# Switch.net
KiCad netlist of a schematic drawn in Altium Designer
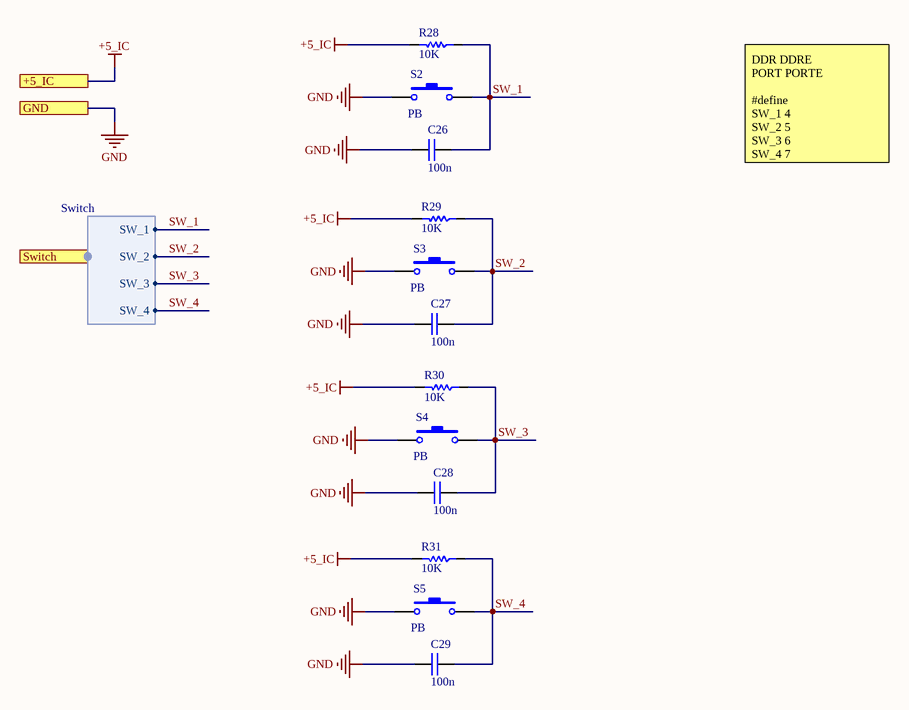
[diagram p0: Switch.SchDoc]

(export (version "E")
  (design (tool "Eeschema 10.0.6"))
  (components
    (comp (ref "C26")
      (value "100n")
      (footprint "CAP 1206/3216")
      (description "Bipolar ceramic capacitor SMD")
      (fields (field (name "VALIDATION") "Valid"))
      (libsource (lib "aKaReZa") (part "Cap_Multi_SMD_100nF_1206"))
    )
    (comp (ref "C27")
      (value "100n")
      (footprint "CAP 1206/3216")
      (description "Bipolar ceramic capacitor SMD")
      (fields (field (name "VALIDATION") "Valid"))
      (libsource (lib "aKaReZa") (part "Cap_Multi_SMD_100nF_1206"))
    )
    (comp (ref "C28")
      (value "100n")
      (footprint "CAP 1206/3216")
      (description "Bipolar ceramic capacitor SMD")
      (fields (field (name "VALIDATION") "Valid"))
      (libsource (lib "aKaReZa") (part "Cap_Multi_SMD_100nF_1206"))
    )
    (comp (ref "C29")
      (value "100n")
      (footprint "CAP 1206/3216")
      (description "Bipolar ceramic capacitor SMD")
      (fields (field (name "VALIDATION") "Valid"))
      (libsource (lib "aKaReZa") (part "Cap_Multi_SMD_100nF_1206"))
    )
    (comp (ref "R28")
      (value "10K")
      (footprint "RES 1206 (3216X08L)")
      (description "Resistor")
      (fields (field (name "VALIDATION") "Valid"))
      (libsource (lib "aKaReZa") (part "Res_SMD_1206"))
    )
    (comp (ref "R29")
      (value "10K")
      (footprint "RES 1206 (3216X08L)")
      (description "Resistor")
      (fields (field (name "VALIDATION") "Valid"))
      (libsource (lib "aKaReZa") (part "Res_SMD_1206"))
    )
    (comp (ref "R30")
      (value "10K")
      (footprint "RES 1206 (3216X08L)")
      (description "Resistor")
      (fields (field (name "VALIDATION") "Valid"))
      (libsource (lib "aKaReZa") (part "Res_SMD_1206"))
    )
    (comp (ref "R31")
      (value "10K")
      (footprint "RES 1206 (3216X08L)")
      (description "Resistor")
      (fields (field (name "VALIDATION") "Valid"))
      (libsource (lib "aKaReZa") (part "Res_SMD_1206"))
    )
    (comp (ref "S2")
      (value "PB")
      (footprint "SW_PB_SMD_2PIN_SPST_6X3X2")
      (description "SMT Tactile ‎Switch")
      (fields (field (name "VALIDATION") "Valid"))
      (libsource (lib "aKaReZa") (part "SW_PushButton_2_SMD"))
    )
    (comp (ref "S3")
      (value "PB")
      (footprint "SW_PB_SMD_2PIN_SPST_6X3X2")
      (description "SMT Tactile ‎Switch")
      (fields (field (name "VALIDATION") "Valid"))
      (libsource (lib "aKaReZa") (part "SW_PushButton_2_SMD"))
    )
    (comp (ref "S4")
      (value "PB")
      (footprint "SW_PB_SMD_2PIN_SPST_6X3X2")
      (description "SMT Tactile ‎Switch")
      (fields (field (name "VALIDATION") "Valid"))
      (libsource (lib "aKaReZa") (part "SW_PushButton_2_SMD"))
    )
    (comp (ref "S5")
      (value "PB")
      (footprint "SW_PB_SMD_2PIN_SPST_6X3X2")
      (description "SMT Tactile ‎Switch")
      (fields (field (name "VALIDATION") "Valid"))
      (libsource (lib "aKaReZa") (part "SW_PushButton_2_SMD"))
    )
  )
  (nets
    (net (code "2") (name "+5_IC") (class "Default")
      (node (ref "R28") (pin "2") (pinfunction "2_2") (pintype "passive"))
      (node (ref "R29") (pin "2") (pinfunction "2_2") (pintype "passive"))
      (node (ref "R30") (pin "2") (pinfunction "2_2") (pintype "passive"))
      (node (ref "R31") (pin "2") (pinfunction "2_2") (pintype "passive"))
    )
    (net (code "3") (name "/SW_1") (class "Default")
      (node (ref "C26") (pin "1") (pinfunction "1_1") (pintype "passive"))
      (node (ref "R28") (pin "1") (pinfunction "1_1") (pintype "passive"))
      (node (ref "S2") (pin "2") (pinfunction "2_2") (pintype "passive"))
    )
    (net (code "4") (name "/SW_2") (class "Default")
      (node (ref "C27") (pin "1") (pinfunction "1_1") (pintype "passive"))
      (node (ref "R29") (pin "1") (pinfunction "1_1") (pintype "passive"))
      (node (ref "S3") (pin "2") (pinfunction "2_2") (pintype "passive"))
    )
    (net (code "5") (name "/SW_3") (class "Default")
      (node (ref "C28") (pin "1") (pinfunction "1_1") (pintype "passive"))
      (node (ref "R30") (pin "1") (pinfunction "1_1") (pintype "passive"))
      (node (ref "S4") (pin "2") (pinfunction "2_2") (pintype "passive"))
    )
    (net (code "6") (name "/SW_4") (class "Default")
      (node (ref "C29") (pin "1") (pinfunction "1_1") (pintype "passive"))
      (node (ref "R31") (pin "1") (pinfunction "1_1") (pintype "passive"))
      (node (ref "S5") (pin "2") (pinfunction "2_2") (pintype "passive"))
    )
    (net (code "8") (name "GND") (class "Default")
      (node (ref "C26") (pin "2") (pinfunction "2_2") (pintype "passive"))
      (node (ref "C27") (pin "2") (pinfunction "2_2") (pintype "passive"))
      (node (ref "C28") (pin "2") (pinfunction "2_2") (pintype "passive"))
      (node (ref "C29") (pin "2") (pinfunction "2_2") (pintype "passive"))
      (node (ref "S2") (pin "1") (pinfunction "1_1") (pintype "passive"))
      (node (ref "S3") (pin "1") (pinfunction "1_1") (pintype "passive"))
      (node (ref "S4") (pin "1") (pinfunction "1_1") (pintype "passive"))
      (node (ref "S5") (pin "1") (pinfunction "1_1") (pintype "passive"))
    )
  )
)
